# HV_DAC_1PPM.net
KiCad netlist of a schematic drawn in Altium Designer
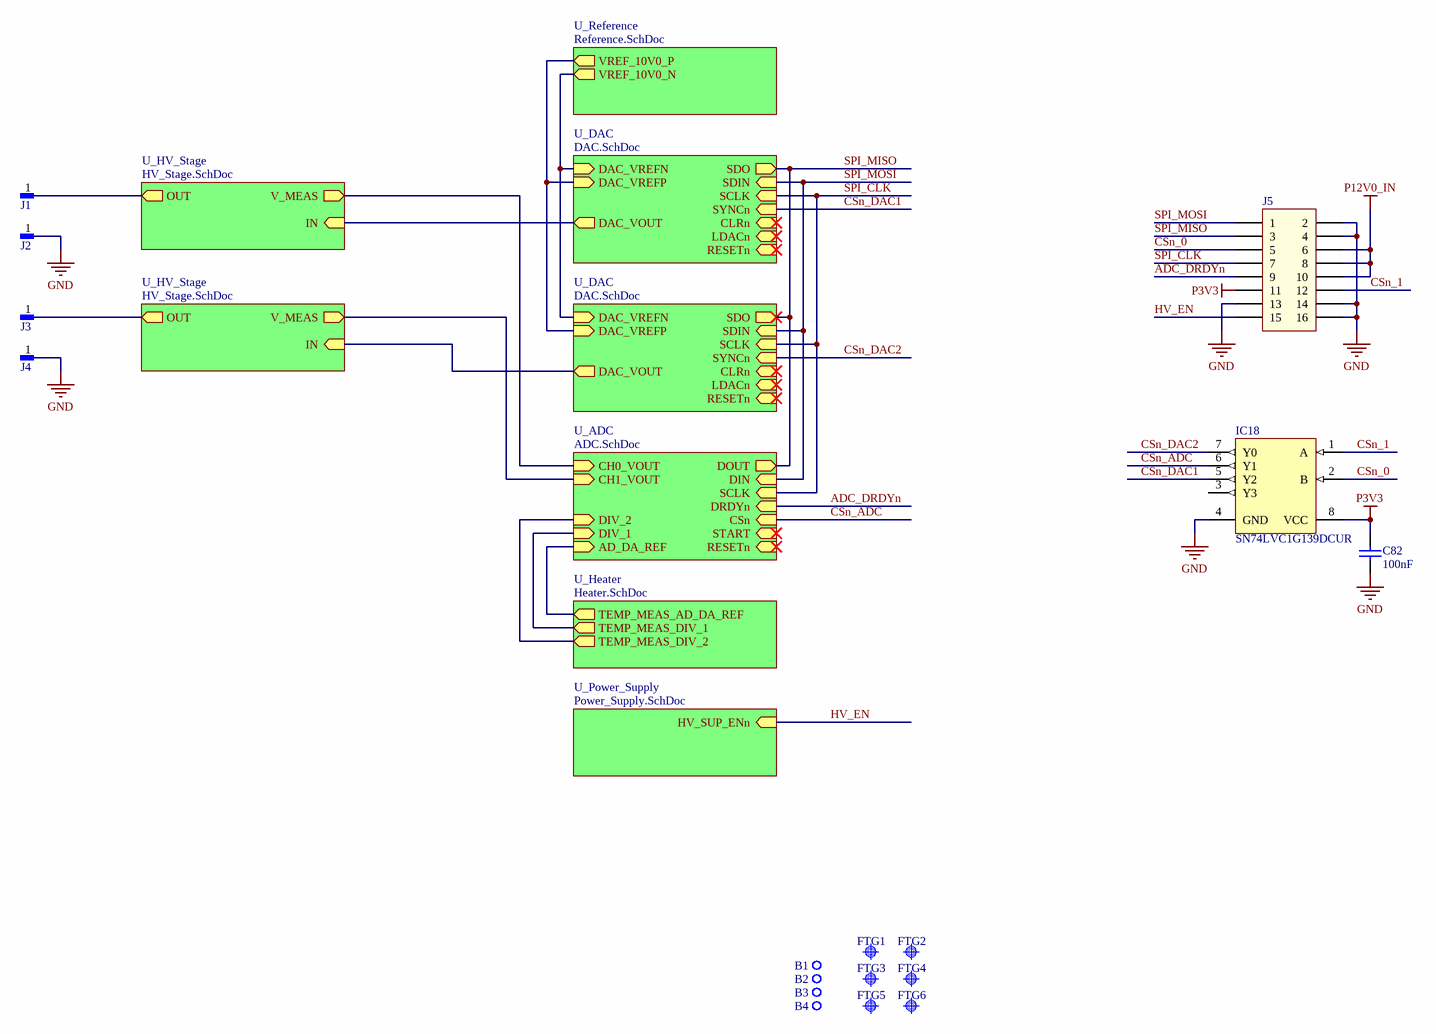
[diagram p0: HV_DAC_1PPM.SchDoc]

(export (version "E")
  (design (tool "Eeschema 10.0.6"))
  (components
    (comp (ref "B1")
      (value "Plated Hole")
      (footprint "MTG270_500")
      (description "Single Terminal Socket")
      (fields (field (name "PART NUMBER") "PLATED_HOLE2.7_PAD5.0") (field (name "AUTHOR") "CERN DEM JMW"))
      (libsource (lib "Eletro-mechanical") (part "Single Terminal Socket"))
    )
    (comp (ref "B2")
      (value "Plated Hole")
      (footprint "MTG270_500")
      (description "Single Terminal Socket")
      (fields (field (name "PART NUMBER") "PLATED_HOLE2.7_PAD5.0") (field (name "AUTHOR") "CERN DEM JMW"))
      (libsource (lib "Eletro-mechanical") (part "Single Terminal Socket"))
    )
    (comp (ref "B3")
      (value "Plated Hole")
      (footprint "MTG270_500")
      (description "Single Terminal Socket")
      (fields (field (name "PART NUMBER") "PLATED_HOLE2.7_PAD5.0") (field (name "AUTHOR") "CERN DEM JMW"))
      (libsource (lib "Eletro-mechanical") (part "Single Terminal Socket"))
    )
    (comp (ref "B4")
      (value "Plated Hole")
      (footprint "MTG270_500")
      (description "Single Terminal Socket")
      (fields (field (name "PART NUMBER") "PLATED_HOLE2.7_PAD5.0") (field (name "AUTHOR") "CERN DEM JMW"))
      (libsource (lib "Eletro-mechanical") (part "Single Terminal Socket"))
    )
    (comp (ref "C82")
      (value "100nF")
      (footprint "CAPC1005X55N")
      (description "Non-polarised capacitor")
      (fields
        (field (name "PART NUMBER") "CC0402_100NF_50V_10%_X7R")
        (field (name "VOLTAGE") "50V")
        (field (name "AUTHOR") "CERN DEM MR")
      )
      (libsource (lib "Capacitors") (part "Capacitor - non polarized"))
    )
    (comp (ref "FTG1")
      (value "Use only in PCB")
      (footprint "FIDUCIAL_TOP_S100-200")
      (description "Fiducial Target")
      (fields (field (name "PART NUMBER") "FIDUCIAL_TARGET_S100-200") (field (name "AUTHOR") "CERN DEM JLC"))
      (libsource (lib "Eletro-mechanical") (part "Fiducial Target"))
    )
    (comp (ref "FTG2")
      (value "Use only in PCB")
      (footprint "FIDUCIAL_TOP_S100-200")
      (description "Fiducial Target")
      (fields (field (name "PART NUMBER") "FIDUCIAL_TARGET_S100-200") (field (name "AUTHOR") "CERN DEM JLC"))
      (libsource (lib "Eletro-mechanical") (part "Fiducial Target"))
    )
    (comp (ref "FTG3")
      (value "Use only in PCB")
      (footprint "FIDUCIAL_TOP_S100-200")
      (description "Fiducial Target")
      (fields (field (name "PART NUMBER") "FIDUCIAL_TARGET_S100-200") (field (name "AUTHOR") "CERN DEM JLC"))
      (libsource (lib "Eletro-mechanical") (part "Fiducial Target"))
    )
    (comp (ref "FTG4")
      (value "Use only in PCB")
      (footprint "FIDUCIAL_TOP_S100-200")
      (description "Fiducial Target")
      (fields (field (name "PART NUMBER") "FIDUCIAL_TARGET_S100-200") (field (name "AUTHOR") "CERN DEM JLC"))
      (libsource (lib "Eletro-mechanical") (part "Fiducial Target"))
    )
    (comp (ref "FTG5")
      (value "Use only in PCB")
      (footprint "FIDUCIAL_TOP_S100-200")
      (description "Fiducial Target")
      (fields (field (name "PART NUMBER") "FIDUCIAL_TARGET_S100-200") (field (name "AUTHOR") "CERN DEM JLC"))
      (libsource (lib "Eletro-mechanical") (part "Fiducial Target"))
    )
    (comp (ref "FTG6")
      (value "Use only in PCB")
      (footprint "FIDUCIAL_TOP_S100-200")
      (description "Fiducial Target")
      (fields (field (name "PART NUMBER") "FIDUCIAL_TARGET_S100-200") (field (name "AUTHOR") "CERN DEM JLC"))
      (libsource (lib "Eletro-mechanical") (part "Fiducial Target"))
    )
    (comp (ref "IC18")
      (value "SN74LVC1G139DCUR")
      (footprint "TSSOP50P310X90-8N")
      (description "IC DECODER/DEMUX 1X2: 4 8VSSOP Decoder/Demultiplexer 1 x 2: 4 8-VSSOP")
      (fields (field (name "MANUFACTURER") "Texas Instruments"))
      (libsource (lib "mb") (part "SN74LVC1G139DCUR"))
    )
    (comp (ref "J1")
      (value "SMD Pad")
      (footprint "R400X300")
      (description "Pad")
      (fields (field (name "PART NUMBER") "SMD_PAD_4X3MM") (field (name "AUTHOR") "CERN DEM JLC"))
      (libsource (lib "Eletro-mechanical") (part "Single SMD Pad"))
    )
    (comp (ref "J2")
      (value "SMD Pad")
      (footprint "R400X300")
      (description "Pad")
      (fields (field (name "PART NUMBER") "SMD_PAD_4X3MM") (field (name "AUTHOR") "CERN DEM JLC"))
      (libsource (lib "Eletro-mechanical") (part "Single SMD Pad"))
    )
    (comp (ref "J3")
      (value "SMD Pad")
      (footprint "R400X300")
      (description "Pad")
      (fields (field (name "PART NUMBER") "SMD_PAD_4X3MM") (field (name "AUTHOR") "CERN DEM JLC"))
      (libsource (lib "Eletro-mechanical") (part "Single SMD Pad"))
    )
    (comp (ref "J4")
      (value "SMD Pad")
      (footprint "R400X300")
      (description "Pad")
      (fields (field (name "PART NUMBER") "SMD_PAD_4X3MM") (field (name "AUTHOR") "CERN DEM JLC"))
      (libsource (lib "Eletro-mechanical") (part "Single SMD Pad"))
    )
    (comp (ref "J5")
      (value "2.00 mm_SMT_Vertical_16 pin")
      (footprint "62131621821")
      (description "Socket Header WR-PHD, Pitch 2.00 mm, SMT, Vertical, dual row, 16 pin")
      (fields (field (name "PART NUMBER") "62131621821") (field (name "PUBLISHER") "Wurth Elektronik"))
      (libsource (lib "ALTIUM-PHD_2_0_SMT_DUAL_SOCKET_HEADER_LOW_PROFILE_REEL_6213XX21821-rev18a") (part "62131621821"))
    )
  )
  (nets
    (net (code "1") (name "/ADC_DRDYn") (class "Default")
      (node (ref "J5") (pin "9") (pinfunction "9_9") (pintype "passive"))
    )
    (net (code "4") (name "/CSn_0") (class "Default")
      (node (ref "IC18") (pin "2") (pinfunction "B_2") (pintype "input"))
      (node (ref "J5") (pin "5") (pinfunction "5_5") (pintype "passive"))
    )
    (net (code "5") (name "/CSn_1") (class "Default")
      (node (ref "IC18") (pin "1") (pinfunction "A_1") (pintype "input"))
      (node (ref "J5") (pin "12") (pinfunction "12_12") (pintype "passive"))
    )
    (net (code "6") (name "/CSn_ADC") (class "Default")
      (node (ref "IC18") (pin "6") (pinfunction "Y1_6") (pintype "output"))
    )
    (net (code "7") (name "/CSn_DAC1") (class "Default")
      (node (ref "IC18") (pin "5") (pinfunction "Y2_5") (pintype "output"))
    )
    (net (code "8") (name "/CSn_DAC2") (class "Default")
      (node (ref "IC18") (pin "7") (pinfunction "Y0_7") (pintype "output"))
    )
    (net (code "11") (name "/HV_EN") (class "Default")
      (node (ref "J5") (pin "15") (pinfunction "15_15") (pintype "passive"))
    )
    (net (code "14") (name "/OUT") (class "Default")
      (node (ref "J1") (pin "1") (pinfunction "1_1") (pintype "bidirectional"))
    )
    (net (code "15") (name "/OUT_1") (class "Default")
      (node (ref "J3") (pin "1") (pinfunction "1_1") (pintype "bidirectional"))
    )
    (net (code "19") (name "/SPI_CLK") (class "Default")
      (node (ref "J5") (pin "7") (pinfunction "7_7") (pintype "passive"))
    )
    (net (code "20") (name "/SPI_MISO") (class "Default")
      (node (ref "J5") (pin "3") (pinfunction "3_3") (pintype "passive+no_connect"))
    )
    (net (code "21") (name "/SPI_MOSI") (class "Default")
      (node (ref "J5") (pin "1") (pinfunction "1_1") (pintype "passive"))
    )
    (net (code "30") (name "GND") (class "Default")
      (node (ref "C82") (pin "1") (pinfunction "1_1") (pintype "passive"))
      (node (ref "IC18") (pin "4") (pinfunction "GND_4") (pintype "power_in"))
      (node (ref "J2") (pin "1") (pinfunction "1_1") (pintype "bidirectional"))
      (node (ref "J4") (pin "1") (pinfunction "1_1") (pintype "bidirectional"))
      (node (ref "J5") (pin "13") (pinfunction "13_13") (pintype "passive"))
      (node (ref "J5") (pin "14") (pinfunction "14_14") (pintype "passive"))
      (node (ref "J5") (pin "16") (pinfunction "16_16") (pintype "passive"))
      (node (ref "J5") (pin "2") (pinfunction "2_2") (pintype "passive"))
      (node (ref "J5") (pin "4") (pinfunction "4_4") (pintype "passive"))
    )
    (net (code "31") (name "P3V3") (class "Default")
      (node (ref "C82") (pin "2") (pinfunction "2_2") (pintype "passive"))
      (node (ref "IC18") (pin "8") (pinfunction "VCC_8") (pintype "power_in"))
      (node (ref "J5") (pin "11") (pinfunction "11_11") (pintype "passive"))
    )
    (net (code "32") (name "P12V0_IN") (class "Default")
      (node (ref "J5") (pin "10") (pinfunction "10_10") (pintype "passive"))
      (node (ref "J5") (pin "6") (pinfunction "6_6") (pintype "passive"))
      (node (ref "J5") (pin "8") (pinfunction "8_8") (pintype "passive"))
    )
    (net (code "33") (name "unconnected-(B1-Pad1)") (class "Default")
      (node (ref "B1") (pin "1") (pinfunction "1_1") (pintype "bidirectional"))
    )
    (net (code "34") (name "unconnected-(B2-Pad1)") (class "Default")
      (node (ref "B2") (pin "1") (pinfunction "1_1") (pintype "bidirectional"))
    )
    (net (code "35") (name "unconnected-(B3-Pad1)") (class "Default")
      (node (ref "B3") (pin "1") (pinfunction "1_1") (pintype "bidirectional"))
    )
    (net (code "36") (name "unconnected-(B4-Pad1)") (class "Default")
      (node (ref "B4") (pin "1") (pinfunction "1_1") (pintype "bidirectional"))
    )
    (net (code "37") (name "unconnected-(IC18-Y3-Pad3)") (class "Default")
      (node (ref "IC18") (pin "3") (pinfunction "Y3_3") (pintype "output"))
    )
  )
)
